# CV_LEDControl.net
KiCad netlist of a schematic drawn in EAGLE
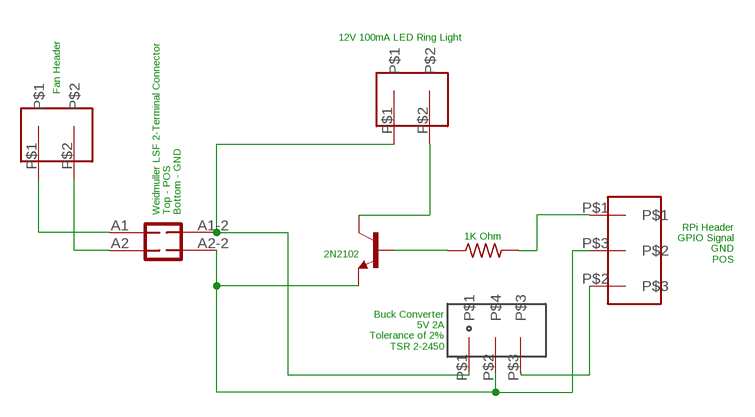
[diagram p0: schematic, sheet 1]

(export (version "E")
  (design (tool "Eeschema 10.0.6"))
  (components
    (comp (ref "R1")
      (value "R-US_0204/7")
      (footprint "eagle-import:0204_7")
      (libsource (lib "eagle-import") (part "R-US_0204/7"))
    )
    (comp (ref "T1")
      (value "2N2102")
      (footprint "eagle-import:TO5")
      (libsource (lib "eagle-import") (part "2N2102"))
    )
    (comp (ref "U$1")
      (value "TSR2-2450")
      (footprint "eagle-import:TSR2")
      (libsource (lib "eagle-import") (part "TSR2-2450"))
    )
    (comp (ref "U$2")
      (value "2-PORTTERMINAL-26AWG")
      (footprint "eagle-import:2-PORTTERMINAL-26AWG")
      (libsource (lib "eagle-import") (part "2-PORTTERMINAL-26AWG"))
    )
    (comp (ref "U$3")
      (value "2-PORTTERMINAL-22AWG")
      (footprint "eagle-import:2-PORTTERMINAL-22AWG")
      (libsource (lib "eagle-import") (part "2-PORTTERMINAL-22AWG"))
    )
    (comp (ref "U$4")
      (value "3-PORTTERMINAL-22AWG")
      (footprint "eagle-import:3-PORTTERMINAL-22AWG")
      (libsource (lib "eagle-import") (part "3-PORTTERMINAL-22AWG"))
    )
    (comp (ref "WEIDMULLERLSF")
      (value "WEIDMUELLER_1824420000WEIDMUELLER_1824420000_0_0")
      (footprint "eagle-import:WEIDMUELLER_1824420000_0")
      (fields (field (name "MF") "Weidmueller") (field (name "MPN") "1824420000"))
      (libsource (lib "eagle-import") (part "WEIDMUELLER_1824420000WEIDMUELLER_1824420000_0_0"))
    )
  )
  (nets
    (net (code "1") (name "Net-(R1-Pad2)") (class "Default")
      (node (ref "R1") (pin "2") (pinfunction "2_2") (pintype "passive"))
      (node (ref "U$4") (pin "P$1") (pinfunction "P$1_P$1") (pintype "bidirectional"))
    )
    (net (code "2") (name "Net-(T1-B)") (class "Default")
      (node (ref "R1") (pin "1") (pinfunction "1_1") (pintype "passive"))
      (node (ref "T1") (pin "2") (pinfunction "B_2") (pintype "passive"))
    )
    (net (code "3") (name "Net-(T1-C)") (class "Default")
      (node (ref "T1") (pin "3") (pinfunction "C_3") (pintype "passive"))
      (node (ref "U$3") (pin "P$2") (pinfunction "P$2_P$2") (pintype "bidirectional"))
    )
    (net (code "4") (name "Net-(T1-E)") (class "Default")
      (node (ref "T1") (pin "1") (pinfunction "E_1") (pintype "passive"))
      (node (ref "U$1") (pin "P$2") (pinfunction "P$4_P$2") (pintype "bidirectional"))
      (node (ref "U$4") (pin "P$3") (pinfunction "P$2_P$3") (pintype "bidirectional"))
      (node (ref "WEIDMULLERLSF") (pin "A2-2") (pinfunction "A2_A2-2") (pintype "passive"))
    )
    (net (code "5") (name "Net-(U$4-P$3)") (class "Default")
      (node (ref "U$1") (pin "P$3") (pinfunction "P$3_P$3") (pintype "bidirectional"))
      (node (ref "U$4") (pin "P$2") (pinfunction "P$3_P$2") (pintype "bidirectional"))
    )
    (net (code "6") (name "Net-(WEIDMULLERLSF-A1)") (class "Default")
      (node (ref "U$1") (pin "P$1") (pinfunction "P$1_P$1") (pintype "bidirectional"))
      (node (ref "U$3") (pin "P$1") (pinfunction "P$1_P$1") (pintype "bidirectional"))
      (node (ref "WEIDMULLERLSF") (pin "A1-2") (pinfunction "A1_A1-2") (pintype "passive"))
    )
    (net (code "7") (name "Net-(WEIDMULLERLSF-A3)") (class "Default")
      (node (ref "U$2") (pin "P$2") (pinfunction "P$2_P$2") (pintype "bidirectional"))
      (node (ref "WEIDMULLERLSF") (pin "A2") (pinfunction "A3_A2") (pintype "passive"))
    )
    (net (code "8") (name "Net-(WEIDMULLERLSF-A4)") (class "Default")
      (node (ref "U$2") (pin "P$1") (pinfunction "P$1_P$1") (pintype "bidirectional"))
      (node (ref "WEIDMULLERLSF") (pin "A1") (pinfunction "A4_A1") (pintype "passive"))
    )
  )
)
